# ee207_week_2_lab_diode.net
KiCad netlist of a schematic drawn in Altium Designer
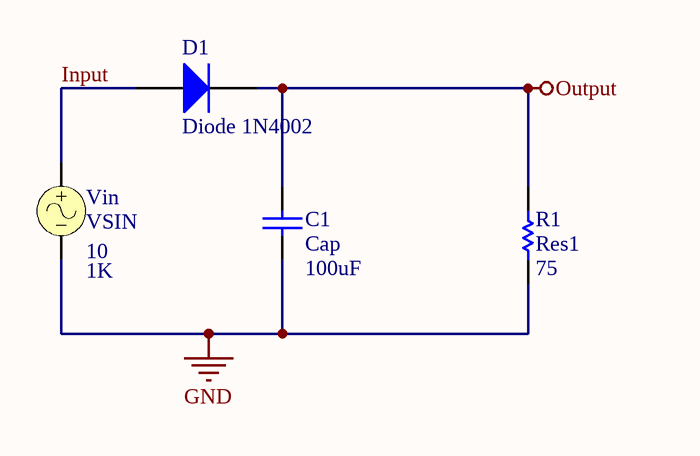
[diagram p0: ee207 week 2 lab diode.SchDoc]

(export (version "E")
  (design (tool "Eeschema 10.0.6"))
  (components
    (comp (ref "C1")
      (value "Cap")
      (footprint "RAD-0.3")
      (description "Capacitor")
      (fields (field (name "ALTIUM_VALUE") "100uF") (field (name "PUBLISHER") "Altium Limited"))
      (libsource (lib "Miscellaneous Devices") (part "Cap"))
    )
    (comp (ref "D1")
      (value "Diode 1N4002")
      (footprint "DO-41")
      (description "1 Amp General Purpose Rectifier")
      (fields (field (name "PUBLISHER") "Altium Limited"))
      (libsource (lib "Miscellaneous Devices") (part "Diode 1N4002"))
    )
    (comp (ref "R1")
      (value "Res1")
      (footprint "AXIAL-0.3")
      (description "Resistor")
      (fields (field (name "ALTIUM_VALUE") "75") (field (name "PUBLISHER") "Altium Limited"))
      (libsource (lib "Miscellaneous Devices") (part "Res1"))
    )
    (comp (ref "Vin")
      (value "VSIN")
      (description "Sinusoidal Voltage Source")
      (fields
        (field (name "AMPLITUDE") "10")
        (field (name "FREQUENCY") "1K")
        (field (name "PUBLISHER") "Altium Limited")
      )
      (libsource (lib "Simulation Sources") (part "VSIN"))
    )
  )
  (nets
    (net (code "1") (name "/Input") (class "Default")
      (node (ref "D1") (pin "1") (pinfunction "A_1") (pintype "passive"))
      (node (ref "Vin") (pin "1") (pinfunction "1_1") (pintype "passive"))
    )
    (net (code "2") (name "GND") (class "Default")
      (node (ref "C1") (pin "1") (pinfunction "1_1") (pintype "passive"))
      (node (ref "R1") (pin "2") (pinfunction "2_2") (pintype "passive"))
      (node (ref "Vin") (pin "2") (pinfunction "2_2") (pintype "passive"))
    )
    (net (code "3") (name "Output") (class "Default")
      (node (ref "C1") (pin "2") (pinfunction "2_2") (pintype "passive"))
      (node (ref "D1") (pin "2") (pinfunction "K_2") (pintype "passive"))
      (node (ref "R1") (pin "1") (pinfunction "1_1") (pintype "passive"))
    )
  )
)
